# Filtr1.net
KiCad netlist of a schematic drawn in Altium Designer
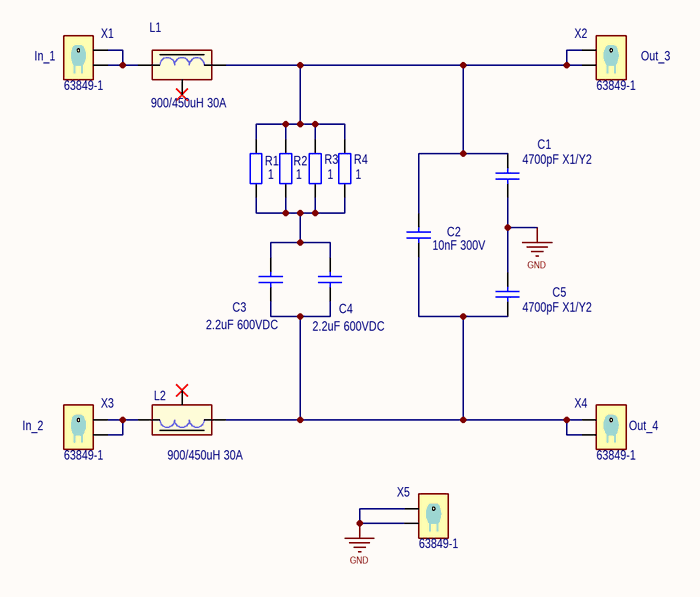
[diagram p0: Filtr1.SchDoc]

(export (version "E")
  (design (tool "Eeschema 10.0.6"))
  (components
    (comp (ref "C1")
      (value "4700pF X1/Y2")
      (footprint "mainLib:SMD_C_2220")
      (description "SMD C2220 MURATA 250Vac 10% X7R X1Y2")
      (fields (field (name "PARTNUMBER") "GA355DR7GF472kW01") (field (name "MANUFACTURER") "MURATA"))
      (libsource (lib "mainRCLib") (part "C X1Y2 4700pF SMD 2220 250Vac 10%"))
    )
    (comp (ref "C2")
      (value "10nF 300V")
      (footprint "mainLib:C Y2 D13 7.5b")
      (description "Ceramic D=14 LS=7.5 300VAC X1Y2")
      (fields (field (name "PARTNUMBER") "DE2F3KY103MA3") (field (name "MANUFACTURER") "Murata"))
      (libsource (lib "mainRCLib") (part "C X1Y2 10nF D13 LS7.5"))
    )
    (comp (ref "C3")
      (value "2.2uF 600VDC")
      (footprint "mainLib:MKP_W20_H39.5_L41.5_LS37.5")
      (description "Polypropelene W20 H39.5 L41.5 LS37.5 600VDC 10%")
      (fields (field (name "PARTNUMBER") "MKP1J042207G00K") (field (name "MANUFACTURER") "Wima"))
      (libsource (lib "mainRCLib") (part "MKP1 2.2uF 10% 600VDC"))
    )
    (comp (ref "C4")
      (value "2.2uF 600VDC")
      (footprint "mainLib:MKP_W20_H39.5_L41.5_LS37.5")
      (description "Polypropelene W20 H39.5 L41.5 LS37.5 600VDC 10%")
      (fields (field (name "PARTNUMBER") "MKP1J042207G00K") (field (name "MANUFACTURER") "Wima"))
      (libsource (lib "mainRCLib") (part "MKP1 2.2uF 10% 600VDC"))
    )
    (comp (ref "C5")
      (value "4700pF X1/Y2")
      (footprint "mainLib:SMD_C_2220")
      (description "SMD C2220 MURATA 250Vac 10% X7R X1Y2")
      (fields (field (name "PARTNUMBER") "GA355DR7GF472kW01") (field (name "MANUFACTURER") "MURATA"))
      (libsource (lib "mainRCLib") (part "C X1Y2 4700pF SMD 2220 250Vac 10%"))
    )
    (comp (ref "L1")
      (value "900/450uH 30A")
      (footprint "mainLib:Dross (900/450 uH) R100230.041.000")
      (description "900/450uH 30A  (Core CK40090 X2)")
      (fields (field (name "MANUFACTURER") "OLTEST") (field (name "PARTNUMBER") "R100.230.041.000"))
      (libsource (lib "mainLib") (part "Dross 900/450uH 30A R100.230.041.000"))
    )
    (comp (ref "L2")
      (value "900/450uH 30A")
      (footprint "mainLib:Dross (900/450 uH) R100230.041.000")
      (description "900/450uH 30A  (Core CK40090 X2)")
      (fields (field (name "MANUFACTURER") "OLTEST") (field (name "PARTNUMBER") "R100.230.041.000"))
      (libsource (lib "") (part "Dross 900/450uH 30A R100.230.041.000_1"))
    )
    (comp (ref "R1")
      (value "1")
      (footprint "mainLib:PRW 5W vertical")
      (description "Выводной PRW 5W 1R +-5%")
      (fields (field (name "PARTNUMBER") "PRW05WJW10J") (field (name "MANUFACTURER") "RoyalOhm"))
      (libsource (lib "mainRCLib") (part "PRW 1 5W +-5%_1"))
    )
    (comp (ref "R2")
      (value "1")
      (footprint "mainLib:PRW 5W vertical")
      (description "Выводной PRW 5W 1R +-5%")
      (fields (field (name "PARTNUMBER") "PRW05WJW10J") (field (name "MANUFACTURER") "RoyalOhm"))
      (libsource (lib "mainRCLib") (part "PRW 1 5W +-5%_1"))
    )
    (comp (ref "R3")
      (value "1")
      (footprint "mainLib:PRW 5W vertical")
      (description "Выводной PRW 5W 1R +-5%")
      (fields (field (name "PARTNUMBER") "PRW05WJW10J") (field (name "MANUFACTURER") "RoyalOhm"))
      (libsource (lib "mainRCLib") (part "PRW 1 5W +-5%_1"))
    )
    (comp (ref "R4")
      (value "1")
      (footprint "mainLib:PRW 5W vertical")
      (description "Выводной PRW 5W 1R +-5%")
      (fields (field (name "PARTNUMBER") "PRW05WJW10J") (field (name "MANUFACTURER") "RoyalOhm"))
      (libsource (lib "mainRCLib") (part "PRW 1 5W +-5%_1"))
    )
    (comp (ref "X1")
      (value "63849-1")
      (footprint "mainLib:63849-1")
      (description "PCB, 6.3х0.8, hole")
      (fields (field (name "MANUFACTURER") "TE Connectivity"))
      (libsource (lib "mainLib") (part "63849-1"))
    )
    (comp (ref "X2")
      (value "63849-1")
      (footprint "mainLib:63849-1")
      (description "PCB, 6.3х0.8, hole")
      (fields (field (name "MANUFACTURER") "TE Connectivity"))
      (libsource (lib "") (part "63849-1_1"))
    )
    (comp (ref "X3")
      (value "63849-1")
      (footprint "mainLib:63849-1")
      (description "PCB, 6.3х0.8, hole")
      (fields (field (name "MANUFACTURER") "TE Connectivity"))
      (libsource (lib "mainLib") (part "63849-1"))
    )
    (comp (ref "X4")
      (value "63849-1")
      (footprint "mainLib:63849-1")
      (description "PCB, 6.3х0.8, hole")
      (fields (field (name "MANUFACTURER") "TE Connectivity"))
      (libsource (lib "") (part "63849-1_1"))
    )
    (comp (ref "X5")
      (value "63849-1")
      (footprint "mainLib:63849-1")
      (description "PCB, 6.3х0.8, hole")
      (fields (field (name "MANUFACTURER") "TE Connectivity"))
      (libsource (lib "") (part "63849-1_1"))
    )
  )
  (nets
    (net (code "1") (name "GND") (class "Default")
      (node (ref "C1") (pin "1") (pinfunction "1_1") (pintype "passive"))
      (node (ref "C5") (pin "2") (pinfunction "2_2") (pintype "passive"))
      (node (ref "X5") (pin "1") (pinfunction "1_1") (pintype "passive"))
      (node (ref "X5") (pin "2") (pinfunction "2_2") (pintype "passive"))
    )
    (net (code "2") (name "Net-(C1-Pad2)") (class "Default")
      (node (ref "C1") (pin "2") (pinfunction "2_2") (pintype "passive"))
      (node (ref "C2") (pin "2") (pinfunction "2_2") (pintype "passive"))
      (node (ref "L1") (pin "2") (pinfunction "2_2") (pintype "passive"))
      (node (ref "R1") (pin "1") (pinfunction "1_1") (pintype "passive"))
      (node (ref "R2") (pin "1") (pinfunction "1_1") (pintype "passive"))
      (node (ref "R3") (pin "1") (pinfunction "1_1") (pintype "passive"))
      (node (ref "R4") (pin "1") (pinfunction "1_1") (pintype "passive"))
      (node (ref "X2") (pin "1") (pinfunction "1_1") (pintype "passive"))
      (node (ref "X2") (pin "2") (pinfunction "2_2") (pintype "passive"))
    )
    (net (code "3") (name "Net-(C2-Pad1)") (class "Default")
      (node (ref "C2") (pin "1") (pinfunction "1_1") (pintype "passive"))
      (node (ref "C3") (pin "2") (pinfunction "2_2") (pintype "passive"))
      (node (ref "C4") (pin "1") (pinfunction "1_1") (pintype "passive"))
      (node (ref "C5") (pin "1") (pinfunction "1_1") (pintype "passive"))
      (node (ref "L2") (pin "2") (pinfunction "2_2") (pintype "passive"))
      (node (ref "X4") (pin "1") (pinfunction "1_1") (pintype "passive"))
      (node (ref "X4") (pin "2") (pinfunction "2_2") (pintype "passive"))
    )
    (net (code "4") (name "Net-(C3-Pad1)") (class "Default")
      (node (ref "C3") (pin "1") (pinfunction "1_1") (pintype "passive"))
      (node (ref "C4") (pin "2") (pinfunction "2_2") (pintype "passive"))
      (node (ref "R1") (pin "2") (pinfunction "2_2") (pintype "passive"))
      (node (ref "R2") (pin "2") (pinfunction "2_2") (pintype "passive"))
      (node (ref "R3") (pin "2") (pinfunction "2_2") (pintype "passive"))
      (node (ref "R4") (pin "2") (pinfunction "2_2") (pintype "passive"))
    )
    (net (code "5") (name "Net-(L1-Pad1)") (class "Default")
      (node (ref "L1") (pin "1") (pinfunction "1_1") (pintype "passive"))
      (node (ref "X1") (pin "1") (pinfunction "1_1") (pintype "passive"))
      (node (ref "X1") (pin "2") (pinfunction "2_2") (pintype "passive"))
    )
    (net (code "6") (name "Net-(L2-Pad1)") (class "Default")
      (node (ref "L2") (pin "1") (pinfunction "1_1") (pintype "passive"))
      (node (ref "X3") (pin "1") (pinfunction "1_1") (pintype "passive"))
      (node (ref "X3") (pin "2") (pinfunction "2_2") (pintype "passive"))
    )
    (net (code "7") (name "unconnected-(L1-Pad3)") (class "Default")
      (node (ref "L1") (pin "3") (pinfunction "3_3") (pintype "passive+no_connect"))
    )
    (net (code "8") (name "unconnected-(L2-Pad3)") (class "Default")
      (node (ref "L2") (pin "3") (pinfunction "3_3") (pintype "passive+no_connect"))
    )
  )
)
